# pca10036_sheet5_power_supply.net
KiCad netlist of a schematic drawn in Altium Designer
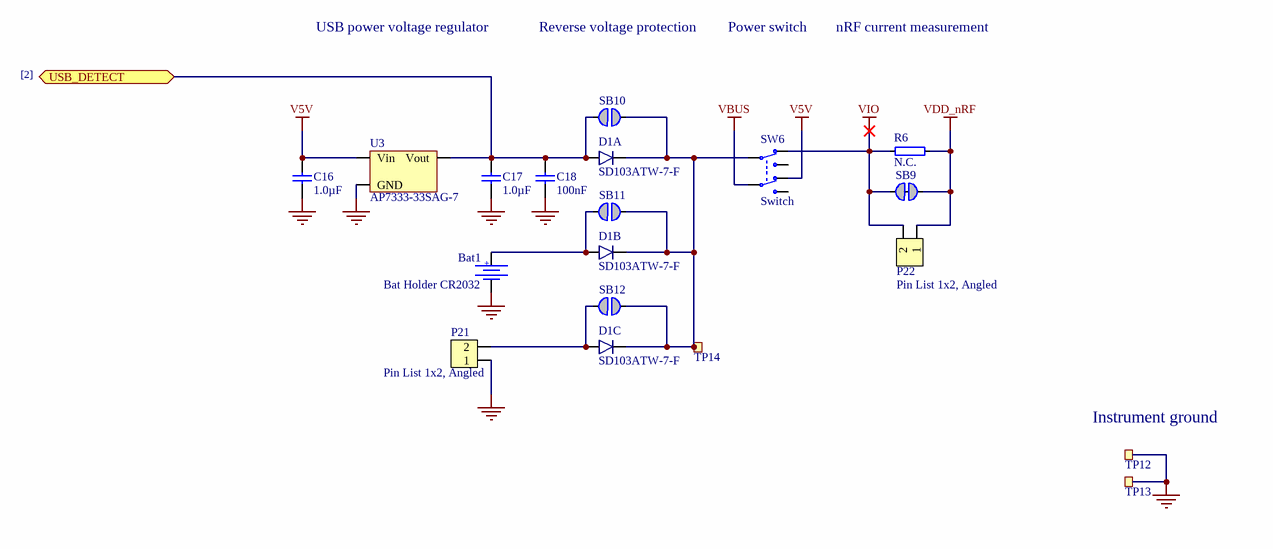
[diagram p0: pca10036_sheet5_power_supply.SchDoc]

(export (version "E")
  (design (tool "Eeschema 10.0.6"))
  (components
    (comp (ref "Bat1")
      (value "Bat Holder CR2032")
      (footprint "CR2032_HOLDER_SMD")
      (description "Bat Holder CR2032 SMD")
      (fields
        (field (name "MANUFACTURER") "Keystone")
        (field (name "MANUFACTURER PART NUMBER") "3002")
        (field (name "PUBLISHER") "Nordic Semiconductor")
      )
      (libsource (lib "Nordic Passive DB") (part "Battery"))
    )
    (comp (ref "C16")
      (value "1.0µF")
      (footprint "CAPC1608X06L")
      (description "Capacitor, X7R, ±10%")
      (fields (field (name "PART NUMBER") "C0603-1µ0") (field (name "PUBLISHER") "Nordic Semiconductor"))
      (libsource (lib "Nordic Passive DB") (part "CAP"))
    )
    (comp (ref "C17")
      (value "1.0µF")
      (footprint "CAPC1608X06L")
      (description "Capacitor, X7R, ±10%")
      (fields (field (name "PART NUMBER") "C0603-1µ0") (field (name "PUBLISHER") "Nordic Semiconductor"))
      (libsource (lib "Nordic Passive DB") (part "CAP"))
    )
    (comp (ref "C18")
      (value "100nF")
      (footprint "CAPC1005X04L")
      (description "Capacitor, X7R, ±10%")
      (fields (field (name "PART NUMBER") "C0402-100n") (field (name "PUBLISHER") "Nordic Semiconductor"))
      (libsource (lib "Nordic Passive DB") (part "CAP"))
    )
    (comp (ref "D1")
      (value "SD103ATW-7-F")
      (footprint "SOT-363")
      (description "Surface Mount Schottky Barrier Diode Array")
      (fields
        (field (name "MANUFACTURER") "Diodes Incorporated")
        (field (name "2ND SOURCE PART NUMBER") "177-3507")
        (field (name "PUBLISHER") "Nordic Semiconductor")
      )
      (libsource (lib "Nordic Discrete DB") (part "D{colon}DIODE_3_IND"))
    )
    (comp (ref "P21")
      (value "Pin List 1x2, Angled")
      (footprint "LIST_ANG_1x2-SMD-2.54MM")
      (description "Pin List 1x2, 2.54mm (100mil), Right Angled, SMD")
      (fields
        (field (name "PART NUMBER") "Pin List Ang 1x2 SMD, 2.54mm")
        (field (name "2ND SOURCE PART NUMBER") "S1113E-02-ND")
        (field (name "PUBLISHER") "Nordic Semiconductor")
      )
      (libsource (lib "Nordic Passive DB") (part "CONN-2"))
    )
    (comp (ref "P22")
      (value "Pin List 1x2, Angled")
      (footprint "LIST_ANG_1x2-SMD-2.54MM")
      (description "Pin List 1x2, 2.54mm (100mil), Right Angled, SMD")
      (fields
        (field (name "PART NUMBER") "Pin List Ang 1x2 SMD, 2.54mm")
        (field (name "2ND SOURCE PART NUMBER") "S1113E-02-ND")
        (field (name "PUBLISHER") "Nordic Semiconductor")
      )
      (libsource (lib "") (part "CONN-2_1"))
    )
    (comp (ref "R6")
      (value "N.C.")
      (footprint "RESC1005X04L")
      (description "Not mounted")
      (fields (field (name "PART NUMBER") "R0402-N.C.") (field (name "PUBLISHER") "Nordic Semiconductor"))
      (libsource (lib "Nordic Passive DB") (part "RES_1"))
    )
    (comp (ref "SB9")
      (value "Solderbridge")
      (footprint "Solderbridge_Shorted")
      (description "Shorted Solderbridge")
      (fields
        (field (name "PART NUMBER") "Solderbridge Shorted")
        (field (name "PUBLISHER") "Nordic Semiconductor")
      )
      (libsource (lib "Nordic Passive DB") (part "SOLDERBRIDGE_SHORTED"))
    )
    (comp (ref "SB10")
      (value "Solderbridge")
      (footprint "Solderbridge")
      (fields (field (name "PUBLISHER") "Nordic Semiconductor"))
      (libsource (lib "Nordic Passive DB") (part "SOLDERBRIDGE"))
    )
    (comp (ref "SB11")
      (value "Solderbridge")
      (footprint "Solderbridge")
      (fields (field (name "PUBLISHER") "Nordic Semiconductor"))
      (libsource (lib "Nordic Passive DB") (part "SOLDERBRIDGE"))
    )
    (comp (ref "SB12")
      (value "Solderbridge")
      (footprint "Solderbridge")
      (fields (field (name "PUBLISHER") "Nordic Semiconductor"))
      (libsource (lib "Nordic Passive DB") (part "SOLDERBRIDGE"))
    )
    (comp (ref "SW6")
      (value "Switch")
      (footprint "JS202011SCQN")
      (description "SMD slide Switch (ON-ON)")
      (fields
        (field (name "PART NUMBER") "JS202011SCQN")
        (field (name "MANUFACTURER") "C&K Components")
        (field (name "PUBLISHER") "Nordic Semiconductor")
      )
      (libsource (lib "Nordic Discrete DB") (part "SW-DPDT"))
    )
    (comp (ref "TP12")
      (value "TP")
      (footprint "TESTPAD-TH")
      (description "Testpoint, through hole")
      (fields (field (name "PART NUMBER") "Testpoint TH") (field (name "PUBLISHER") "Nordic Semiconductor"))
      (libsource (lib "") (part "TESTPAD_1"))
    )
    (comp (ref "TP13")
      (value "TP")
      (footprint "TESTPAD-TH")
      (description "Testpoint, through hole")
      (fields (field (name "PART NUMBER") "Testpoint TH") (field (name "PUBLISHER") "Nordic Semiconductor"))
      (libsource (lib "") (part "TESTPAD_1"))
    )
    (comp (ref "TP14")
      (value "Ø1.0mm,SMD")
      (footprint "TP_SMD_Ø1.0mm")
      (description "1.0mm circular SMD testpad")
      (fields
        (field (name "PART NUMBER") "TP_SMD_Ø1.0MM")
        (field (name "MANUFACTURER") "Nordic Semiconductor")
        (field (name "PUBLISHER") "Nordic Semiconductor")
      )
      (libsource (lib "Nordic Passive DB") (part "TESTPAD"))
    )
    (comp (ref "U3")
      (value "AP7333-33SAG-7")
      (footprint "SOT-23A")
      (description "300mA, Low Quiescent Current, Fast Transient Low Dropout Linear Regulator")
      (fields
        (field (name "MANUFACTURER") "Diodes Incorporated")
        (field (name "PUBLISHER") "Nordic Semiconductor")
      )
      (libsource (lib "Nordic Active DB") (part "AP7333-XXSAG"))
    )
  )
  (nets
    (net (code "1") (name "/USB_DETECT") (class "Default")
      (node (ref "C17") (pin "2") (pinfunction "2_2") (pintype "passive"))
      (node (ref "C18") (pin "2") (pinfunction "2_2") (pintype "passive"))
      (node (ref "D1") (pin "6") (pinfunction "A1_6") (pintype "passive"))
      (node (ref "SB10") (pin "2") (pinfunction "1_2") (pintype "passive"))
      (node (ref "U3") (pin "2") (pinfunction "Vout_2") (pintype "passive"))
    )
    (net (code "2") (name "GND") (class "Default")
      (node (ref "Bat1") (pin "2") (pintype "passive"))
      (node (ref "C16") (pin "1") (pinfunction "1_1") (pintype "passive"))
      (node (ref "C17") (pin "1") (pinfunction "1_1") (pintype "passive"))
      (node (ref "C18") (pin "1") (pinfunction "1_1") (pintype "passive"))
      (node (ref "P21") (pin "1") (pinfunction "1_1") (pintype "passive"))
      (node (ref "TP12") (pin "1") (pinfunction "1_1") (pintype "passive"))
      (node (ref "TP13") (pin "1") (pinfunction "1_1") (pintype "passive"))
      (node (ref "U3") (pin "3") (pinfunction "GND_3") (pintype "passive"))
    )
    (net (code "3") (name "Net-(D1A-C1)") (class "Default")
      (node (ref "D1") (pin "1") (pinfunction "C1_1") (pintype "passive"))
      (node (ref "D1") (pin "2") (pinfunction "C2_2") (pintype "passive"))
      (node (ref "D1") (pin "3") (pinfunction "C3_3") (pintype "passive"))
      (node (ref "SB10") (pin "1") (pinfunction "0_1") (pintype "passive"))
      (node (ref "SB11") (pin "1") (pinfunction "0_1") (pintype "passive"))
      (node (ref "SB12") (pin "1") (pinfunction "0_1") (pintype "passive"))
      (node (ref "SW6") (pin "2") (pinfunction "COM-1_2") (pintype "passive"))
      (node (ref "TP14") (pin "1") (pinfunction "1_1") (pintype "passive"))
    )
    (net (code "4") (name "Net-(D1B-A2)") (class "Default")
      (node (ref "Bat1") (pin "1") (pintype "passive"))
      (node (ref "D1") (pin "5") (pinfunction "A2_5") (pintype "passive"))
      (node (ref "SB11") (pin "2") (pinfunction "1_2") (pintype "passive"))
    )
    (net (code "5") (name "Net-(D1C-A3)") (class "Default")
      (node (ref "D1") (pin "4") (pinfunction "A3_4") (pintype "passive"))
      (node (ref "P21") (pin "2") (pinfunction "2_2") (pintype "passive"))
      (node (ref "SB12") (pin "2") (pinfunction "1_2") (pintype "passive"))
    )
    (net (code "6") (name "V5V") (class "Default")
      (node (ref "C16") (pin "2") (pinfunction "2_2") (pintype "passive"))
      (node (ref "SW6") (pin "6") (pinfunction "N.C-2_6") (pintype "passive"))
      (node (ref "U3") (pin "1") (pinfunction "Vin_1") (pintype "passive"))
    )
    (net (code "7") (name "VBUS") (class "Default")
      (node (ref "SW6") (pin "5") (pinfunction "COM-2_5") (pintype "passive"))
    )
    (net (code "8") (name "VDD_nRF") (class "Default")
      (node (ref "P22") (pin "1") (pinfunction "1_1") (pintype "passive"))
      (node (ref "R6") (pin "2") (pinfunction "2_2") (pintype "passive"))
      (node (ref "SB9") (pin "1") (pinfunction "0_1") (pintype "passive"))
    )
    (net (code "9") (name "VIO") (class "Default")
      (node (ref "P22") (pin "2") (pinfunction "2_2") (pintype "passive"))
      (node (ref "R6") (pin "1") (pinfunction "1_1") (pintype "passive"))
      (node (ref "SB9") (pin "2") (pinfunction "1_2") (pintype "passive"))
      (node (ref "SW6") (pin "3") (pinfunction "N.C-1_3") (pintype "passive"))
    )
    (net (code "10") (name "unconnected-(SW6-N.O-1-Pad1)") (class "Default")
      (node (ref "SW6") (pin "1") (pinfunction "N.O-1_1") (pintype "passive"))
    )
    (net (code "11") (name "unconnected-(SW6-N.O-2-Pad4)") (class "Default")
      (node (ref "SW6") (pin "4") (pinfunction "N.O-2_4") (pintype "passive"))
    )
  )
)
